# Output_Schematic.net
KiCad netlist of a schematic drawn in Altium Designer
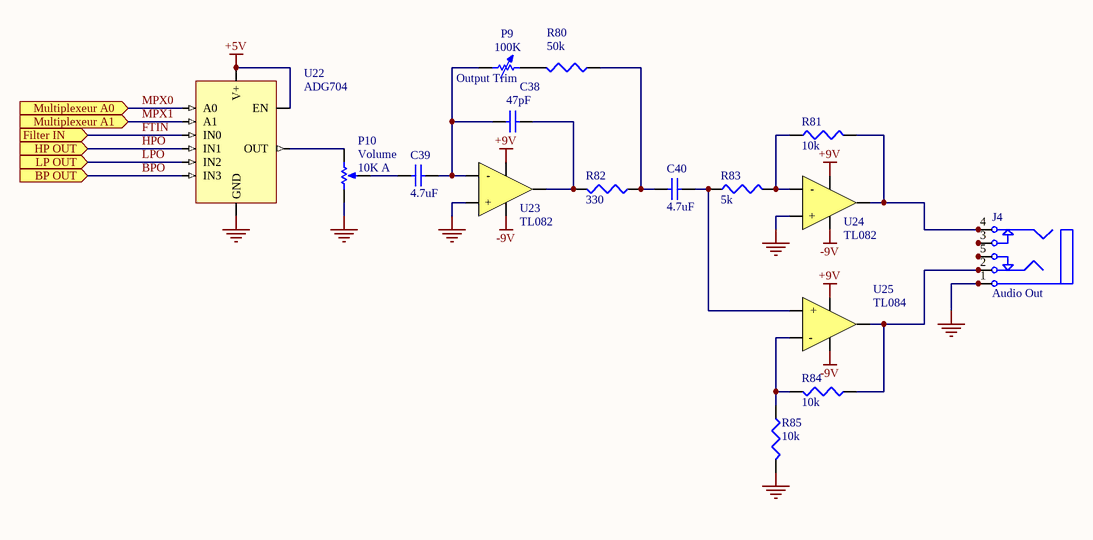
[diagram p0: Output.Schematic.SchDoc]

(export (version "E")
  (design (tool "Eeschema 10.0.6"))
  (components
    (comp (ref "C38")
      (value "47pF")
      (footprint "CAPC1608N")
      (description "Capacitor (Semiconductor SIM Model)")
      (fields (field (name "PUBLISHER") "Altium Limited"))
      (libsource (lib "Miscellaneous Devices") (part "Cap Semi"))
    )
    (comp (ref "C39")
      (value "4.7uF")
      (footprint "CAP1608N")
      (description "Capacitor (Semiconductor SIM Model)")
      (fields (field (name "PUBLISHER") "Altium Limited"))
      (libsource (lib "Miscellaneous Devices") (part "Cap Semi"))
    )
    (comp (ref "C40")
      (value "4.7uF")
      (footprint "CAPC1608N")
      (description "Capacitor (Semiconductor SIM Model)")
      (fields (field (name "PUBLISHER") "Altium Limited"))
      (libsource (lib "Miscellaneous Devices") (part "Cap Semi"))
    )
    (comp (ref "J4")
      (value "Audio Out")
      (footprint "ST-3150-5N")
      (description "3-Conductor Jack with 2 break contacts (normals) and 2 auxiliary make contacts")
      (fields (field (name "PUBLISHER") "Altium Limited"))
      (libsource (lib "Miscellaneous Connectors") (part "Phonejack Stereo SW"))
    )
    (comp (ref "P9")
      (value "Output Trim")
      (footprint "AXIAL-0.7")
      (description "Variable Resistor")
      (fields (field (name "ALTIUM_VALUE") "100K") (field (name "PUBLISHER") "Altium Limited"))
      (libsource (lib "Miscellaneous Devices") (part "Res Adj1"))
    )
    (comp (ref "P10")
      (value "Volume")
      (footprint "VR5")
      (description "Potentiometer")
      (fields (field (name "ALTIUM_VALUE") "10K A") (field (name "PUBLISHER") "Altium Limited"))
      (libsource (lib "Miscellaneous Devices") (part "RPot"))
    )
    (comp (ref "R80")
      (value "50k")
      (footprint "CAPC1608N")
      (description "Resistor")
      (fields (field (name "PUBLISHER") "Altium Limited"))
      (libsource (lib "Miscellaneous Devices") (part "Res3"))
    )
    (comp (ref "R81")
      (value "10k")
      (footprint "CAPC1608N")
      (description "Resistor")
      (fields (field (name "PUBLISHER") "Altium Limited"))
      (libsource (lib "Miscellaneous Devices") (part "Res3"))
    )
    (comp (ref "R82")
      (value "330")
      (footprint "CAPC1608N")
      (description "Resistor")
      (fields (field (name "PUBLISHER") "Altium Limited"))
      (libsource (lib "Miscellaneous Devices") (part "Res3"))
    )
    (comp (ref "R83")
      (value "5k")
      (footprint "CAPC1608N")
      (description "Resistor")
      (fields (field (name "PUBLISHER") "Altium Limited"))
      (libsource (lib "Miscellaneous Devices") (part "Res3"))
    )
    (comp (ref "R84")
      (value "10k")
      (footprint "J1-0603")
      (description "Resistor")
      (fields (field (name "PUBLISHER") "Altium Limited"))
      (libsource (lib "Miscellaneous Devices") (part "Res3"))
    )
    (comp (ref "R85")
      (value "10k")
      (footprint "RESC6332")
      (description "Resistor")
      (fields (field (name "PUBLISHER") "Altium Limited"))
      (libsource (lib "Miscellaneous Devices") (part "Res3"))
    )
    (comp (ref "U22") (value "ADG704") (libsource (lib "SynthyTwo.Components") (part "ADG704")))
    (comp (ref "U23") (value "TL082") (libsource (lib "SynthyTwo.Components") (part "TL082")))
    (comp (ref "U24") (value "TL082") (libsource (lib "SynthyTwo.Components") (part "TL082")))
    (comp (ref "U25") (value "TL084") (libsource (lib "SynthyTwo.Components") (part "TL084")))
  )
  (nets
    (net (code "1") (name "+5V") (class "Default")
      (node (ref "U22") (pin "5") (pinfunction "EN_5") (pintype "passive"))
      (node (ref "U22") (pin "6") (pinfunction "V+_6") (pintype "power_in"))
    )
    (net (code "2") (name "+9V") (class "Default")
      (node (ref "U23") (pin "8") (pinfunction "VCC+_8") (pintype "passive"))
      (node (ref "U24") (pin "8") (pinfunction "VCC+_8") (pintype "passive"))
      (node (ref "U25") (pin "4") (pinfunction "VCC+_4") (pintype "passive"))
    )
    (net (code "3") (name "-9V") (class "Default")
      (node (ref "U23") (pin "4") (pinfunction "VCC-_4") (pintype "passive"))
      (node (ref "U24") (pin "4") (pinfunction "VCC-_4") (pintype "passive"))
      (node (ref "U25") (pin "11") (pinfunction "VCC-_11") (pintype "passive"))
    )
    (net (code "4") (name "/BPO") (class "Default")
      (node (ref "U22") (pin "7") (pinfunction "IN3_7") (pintype "input"))
    )
    (net (code "5") (name "/FTIN") (class "Default")
      (node (ref "U22") (pin "2") (pinfunction "IN0_2") (pintype "input"))
    )
    (net (code "6") (name "/HPO") (class "Default")
      (node (ref "U22") (pin "9") (pinfunction "IN1_9") (pintype "input"))
    )
    (net (code "7") (name "/LPO") (class "Default")
      (node (ref "U22") (pin "4") (pinfunction "IN2_4") (pintype "input"))
    )
    (net (code "8") (name "/MPX0") (class "Default")
      (node (ref "U22") (pin "1") (pinfunction "A0_1") (pintype "input"))
    )
    (net (code "9") (name "/MPX1") (class "Default")
      (node (ref "U22") (pin "10") (pinfunction "A1_10") (pintype "input"))
    )
    (net (code "10") (name "GND") (class "Default")
      (node (ref "J4") (pin "1") (pinfunction "1_1") (pintype "passive"))
      (node (ref "J4") (pin "1A") (pinfunction "1A_1A") (pintype "passive"))
      (node (ref "J4") (pin "1B") (pinfunction "1B_1B") (pintype "passive"))
      (node (ref "P10") (pin "1") (pinfunction "TOP_1") (pintype "passive"))
      (node (ref "R85") (pin "2") (pinfunction "2_2") (pintype "passive"))
      (node (ref "U22") (pin "3") (pinfunction "GND_3") (pintype "power_in"))
      (node (ref "U23") (pin "3") (pinfunction "+_3") (pintype "passive"))
      (node (ref "U24") (pin "3") (pinfunction "+_3") (pintype "passive"))
    )
    (net (code "11") (name "Net-(C40-Pad1)") (class "Default")
      (node (ref "C40") (pin "1") (pinfunction "1_1") (pintype "passive"))
      (node (ref "R80") (pin "1") (pinfunction "1_1") (pintype "passive"))
      (node (ref "R82") (pin "1") (pinfunction "1_1") (pintype "passive"))
    )
    (net (code "12") (name "Net-(J4-Pad3)") (class "Default")
      (node (ref "J4") (pin "3") (pinfunction "3_3") (pintype "passive"))
      (node (ref "J4") (pin "3A") (pinfunction "3A_3A") (pintype "passive"))
      (node (ref "J4") (pin "3B") (pinfunction "3B_3B") (pintype "passive"))
    )
    (net (code "13") (name "Net-(J4-Pad5)") (class "Default")
      (node (ref "J4") (pin "5") (pinfunction "5_5") (pintype "passive"))
      (node (ref "J4") (pin "5A") (pinfunction "5A_5A") (pintype "passive"))
      (node (ref "J4") (pin "5B") (pinfunction "5B_5B") (pintype "passive"))
    )
    (net (code "14") (name "Net-(P9-Pad2)") (class "Default")
      (node (ref "P9") (pin "2") (pinfunction "2_2") (pintype "passive"))
      (node (ref "R80") (pin "2") (pinfunction "2_2") (pintype "passive"))
    )
    (net (code "15") (name "Net-(P10-BOT)") (class "Default")
      (node (ref "P10") (pin "2") (pinfunction "BOT_2") (pintype "passive"))
      (node (ref "U22") (pin "8") (pinfunction "OUT_8") (pintype "output"))
    )
    (net (code "16") (name "Net-(P10-TAP)") (class "Default")
      (node (ref "C39") (pin "1") (pinfunction "1_1") (pintype "passive"))
      (node (ref "P10") (pin "3") (pinfunction "TAP_3") (pintype "passive"))
    )
    (net (code "17") (name "Net-(U23--)") (class "Default")
      (node (ref "C38") (pin "1") (pinfunction "1_1") (pintype "passive"))
      (node (ref "C39") (pin "2") (pinfunction "2_2") (pintype "passive"))
      (node (ref "P9") (pin "1") (pinfunction "1_1") (pintype "passive"))
      (node (ref "U23") (pin "2") (pinfunction "-_2") (pintype "passive"))
    )
    (net (code "18") (name "Net-(U23-OUT)") (class "Default")
      (node (ref "C38") (pin "2") (pinfunction "2_2") (pintype "passive"))
      (node (ref "R82") (pin "2") (pinfunction "2_2") (pintype "passive"))
      (node (ref "U23") (pin "1") (pinfunction "OUT_1") (pintype "passive"))
    )
    (net (code "19") (name "Net-(U24--)") (class "Default")
      (node (ref "R81") (pin "1") (pinfunction "1_1") (pintype "passive"))
      (node (ref "R83") (pin "2") (pinfunction "2_2") (pintype "passive"))
      (node (ref "U24") (pin "2") (pinfunction "-_2") (pintype "passive"))
    )
    (net (code "20") (name "Net-(U24-OUT)") (class "Default")
      (node (ref "J4") (pin "4") (pinfunction "4_4") (pintype "passive"))
      (node (ref "J4") (pin "4A") (pinfunction "4A_4A") (pintype "passive"))
      (node (ref "J4") (pin "4B") (pinfunction "4B_4B") (pintype "passive"))
      (node (ref "R81") (pin "2") (pinfunction "2_2") (pintype "passive"))
      (node (ref "U24") (pin "1") (pinfunction "OUT_1") (pintype "passive"))
    )
    (net (code "21") (name "Net-(U25-+)") (class "Default")
      (node (ref "C40") (pin "2") (pinfunction "2_2") (pintype "passive"))
      (node (ref "R83") (pin "1") (pinfunction "1_1") (pintype "passive"))
      (node (ref "U25") (pin "2") (pinfunction "+_2") (pintype "passive"))
    )
    (net (code "22") (name "Net-(U25--)") (class "Default")
      (node (ref "R84") (pin "2") (pinfunction "2_2") (pintype "passive"))
      (node (ref "R85") (pin "1") (pinfunction "1_1") (pintype "passive"))
      (node (ref "U25") (pin "3") (pinfunction "-_3") (pintype "passive"))
    )
    (net (code "23") (name "Net-(U25-OUT)") (class "Default")
      (node (ref "J4") (pin "2") (pinfunction "2_2") (pintype "passive"))
      (node (ref "J4") (pin "2A") (pinfunction "2A_2A") (pintype "passive"))
      (node (ref "J4") (pin "2B") (pinfunction "2B_2B") (pintype "passive"))
      (node (ref "R84") (pin "1") (pinfunction "1_1") (pintype "passive"))
      (node (ref "U25") (pin "1") (pinfunction "OUT_1") (pintype "passive"))
    )
  )
)
